# OpenEVSE_PLUS_v1.net
KiCad netlist of a schematic drawn in EAGLE
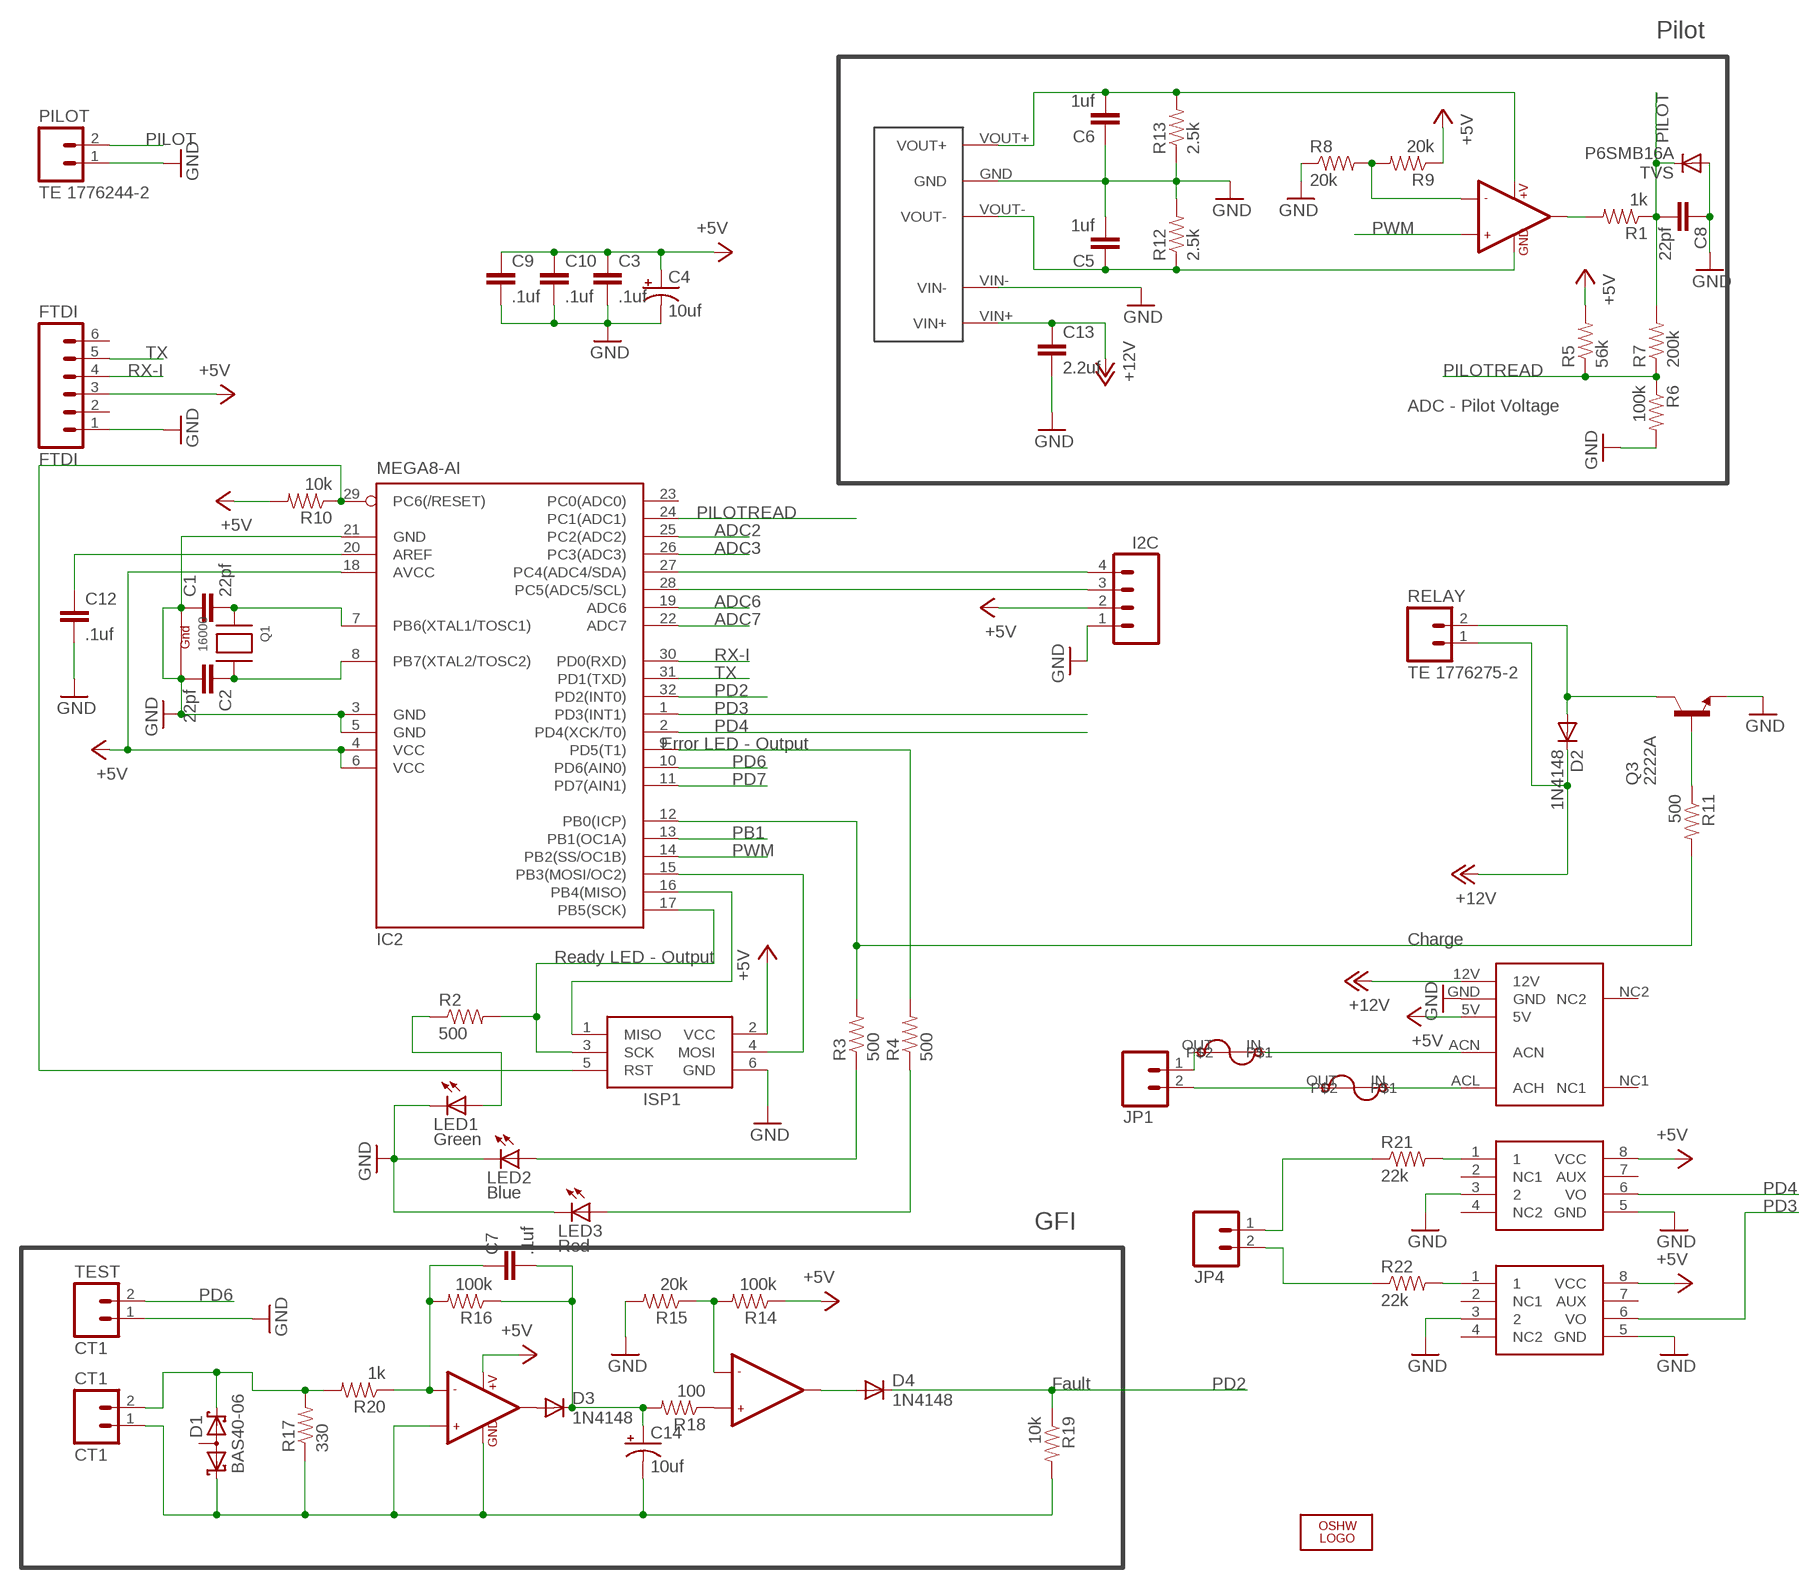
[diagram p0: schematic, sheet 1]

(export (version "E")
  (design (tool "Eeschema 10.0.6"))
  (components
    (comp (ref "C1")
      (value "22pf")
      (footprint "eagle-import:0805")
      (libsource (lib "eagle-import") (part "CAP0805"))
    )
    (comp (ref "C2")
      (value "22pf")
      (footprint "eagle-import:0805")
      (libsource (lib "eagle-import") (part "CAP0805"))
    )
    (comp (ref "C3")
      (value ".1uf")
      (footprint "eagle-import:0805")
      (libsource (lib "eagle-import") (part "CAP0805"))
    )
    (comp (ref "C4")
      (value "10uf")
      (footprint "eagle-import:EIA3216")
      (libsource (lib "eagle-import") (part "CAP_POL1206"))
    )
    (comp (ref "C5")
      (value "1uf")
      (footprint "eagle-import:0805")
      (libsource (lib "eagle-import") (part "CAP0805"))
    )
    (comp (ref "C6")
      (value "1uf")
      (footprint "eagle-import:0805")
      (libsource (lib "eagle-import") (part "CAP0805"))
    )
    (comp (ref "C7")
      (value ".1uf")
      (footprint "eagle-import:0805")
      (libsource (lib "eagle-import") (part "CAP0805"))
    )
    (comp (ref "C8")
      (value "22pf")
      (footprint "eagle-import:0805")
      (libsource (lib "eagle-import") (part "CAP0805"))
    )
    (comp (ref "C9")
      (value ".1uf")
      (footprint "eagle-import:0805")
      (libsource (lib "eagle-import") (part "CAP0805"))
    )
    (comp (ref "C10")
      (value ".1uf")
      (footprint "eagle-import:0805")
      (libsource (lib "eagle-import") (part "CAP0805"))
    )
    (comp (ref "C12")
      (value ".1uf")
      (footprint "eagle-import:0805")
      (libsource (lib "eagle-import") (part "CAP0805"))
    )
    (comp (ref "C13")
      (value "2.2uf")
      (footprint "eagle-import:0805")
      (libsource (lib "eagle-import") (part "CAP0805"))
    )
    (comp (ref "C14")
      (value "10uf")
      (footprint "eagle-import:EIA3216")
      (libsource (lib "eagle-import") (part "CAP_POL1206"))
    )
    (comp (ref "CT1")
      (value "CT1")
      (footprint "eagle-import:1X02_LOCK")
      (libsource (lib "eagle-import") (part "M02LOCK"))
    )
    (comp (ref "D1")
      (value "BAS40-06")
      (footprint "eagle-import:SOT23")
      (libsource (lib "eagle-import") (part "BAS40-06"))
    )
    (comp (ref "D2")
      (value "1N4148")
      (footprint "eagle-import:SOD123")
      (libsource (lib "eagle-import") (part "DIODE-SOD123"))
    )
    (comp (ref "D3")
      (value "1N4148")
      (footprint "eagle-import:SOD123")
      (libsource (lib "eagle-import") (part "DIODE-SOD123"))
    )
    (comp (ref "D4")
      (value "1N4148")
      (footprint "eagle-import:SOD123")
      (libsource (lib "eagle-import") (part "DIODE-SOD123"))
    )
    (comp (ref "DCDC")
      (value "D107E")
      (footprint "eagle-import:DCDC_SIP")
      (libsource (lib "eagle-import") (part "DCDC_SIP"))
    )
    (comp (ref "FTDI")
      (value "FTDI")
      (footprint "eagle-import:1X06_LOCK")
      (libsource (lib "eagle-import") (part "M06LOCK"))
    )
    (comp (ref "I2C")
      (value "M04LOCK")
      (footprint "eagle-import:1X04_LOCK")
      (libsource (lib "eagle-import") (part "M04LOCK"))
    )
    (comp (ref "IC1")
      (value "MID400")
      (footprint "eagle-import:DIP08")
      (libsource (lib "eagle-import") (part "MID400"))
    )
    (comp (ref "IC2")
      (value "MEGA8-AI")
      (footprint "eagle-import:TQFP32-08")
      (fields (field (name "MPN") "ATMEGA8-16AU"))
      (libsource (lib "eagle-import") (part "MEGA8-AI"))
    )
    (comp (ref "IC3")
      (value "LMV358")
      (footprint "eagle-import:SO08")
      (libsource (lib "eagle-import") (part "LMV358"))
    )
    (comp (ref "IC4")
      (value "LMV358")
      (footprint "eagle-import:SO08")
      (libsource (lib "eagle-import") (part "LMV358"))
    )
    (comp (ref "IC5")
      (value "MID400")
      (footprint "eagle-import:DIP08")
      (libsource (lib "eagle-import") (part "MID400"))
    )
    (comp (ref "ISP1")
      (value "AVRISP-6")
      (footprint "eagle-import:AVRISP")
      (libsource (lib "eagle-import") (part "AVRISP-6"))
    )
    (comp (ref "JP1")
      (value "M025MM")
      (footprint "eagle-import:SCREWTERMINAL-5MM-2")
      (libsource (lib "eagle-import") (part "M025MM"))
    )
    (comp (ref "JP4")
      (value "M025MM")
      (footprint "eagle-import:SCREWTERMINAL-5MM-2")
      (libsource (lib "eagle-import") (part "M025MM"))
    )
    (comp (ref "LED1")
      (value "Green")
      (footprint "eagle-import:LED-0603")
      (libsource (lib "eagle-import") (part "LED0603"))
    )
    (comp (ref "LED2")
      (value "Blue")
      (footprint "eagle-import:LED-0603")
      (libsource (lib "eagle-import") (part "LED0603"))
    )
    (comp (ref "LED3")
      (value "Red")
      (footprint "eagle-import:LED-0603")
      (libsource (lib "eagle-import") (part "LED0603"))
    )
    (comp (ref "LOGO1")
      (value "OSHW_LOGO_8MILX0150-NT")
      (footprint "eagle-import:OSHW_8X150_NOTEXT")
      (libsource (lib "eagle-import") (part "OSHW_LOGO_8MILX0150-NT"))
    )
    (comp (ref "PILOT")
      (value "TE 1776244-2")
      (footprint "eagle-import:SCREWTERMINAL-5MM-2")
      (libsource (lib "eagle-import") (part "M025MM"))
    )
    (comp (ref "Q1")
      (value "16000")
      (footprint "eagle-import:NX3225")
      (libsource (lib "eagle-import") (part "XTAL-4-3225"))
    )
    (comp (ref "Q3")
      (value "2222A")
      (footprint "eagle-import:SOT23")
      (libsource (lib "eagle-import") (part "BCX70SMD"))
    )
    (comp (ref "R1")
      (value "1k")
      (footprint "eagle-import:0805")
      (libsource (lib "eagle-import") (part "RESISTOR0805-RES"))
    )
    (comp (ref "R2")
      (value "500")
      (footprint "eagle-import:0805")
      (libsource (lib "eagle-import") (part "RESISTOR0805-RES"))
    )
    (comp (ref "R3")
      (value "500")
      (footprint "eagle-import:0805")
      (libsource (lib "eagle-import") (part "RESISTOR0805-RES"))
    )
    (comp (ref "R4")
      (value "500")
      (footprint "eagle-import:0805")
      (libsource (lib "eagle-import") (part "RESISTOR0805-RES"))
    )
    (comp (ref "R5")
      (value "56k")
      (footprint "eagle-import:0805")
      (libsource (lib "eagle-import") (part "RESISTOR0805-RES"))
    )
    (comp (ref "R6")
      (value "100k")
      (footprint "eagle-import:0805")
      (libsource (lib "eagle-import") (part "RESISTOR0805-RES"))
    )
    (comp (ref "R7")
      (value "200k")
      (footprint "eagle-import:0805")
      (libsource (lib "eagle-import") (part "RESISTOR0805-RES"))
    )
    (comp (ref "R8")
      (value "20k")
      (footprint "eagle-import:0805")
      (libsource (lib "eagle-import") (part "RESISTOR0805-RES"))
    )
    (comp (ref "R9")
      (value "20k")
      (footprint "eagle-import:0805")
      (libsource (lib "eagle-import") (part "RESISTOR0805-RES"))
    )
    (comp (ref "R10")
      (value "10k")
      (footprint "eagle-import:0805")
      (libsource (lib "eagle-import") (part "RESISTOR0805-RES"))
    )
    (comp (ref "R11")
      (value "500")
      (footprint "eagle-import:0805")
      (libsource (lib "eagle-import") (part "RESISTOR0805-RES"))
    )
    (comp (ref "R12")
      (value "2.5k")
      (footprint "eagle-import:0805")
      (libsource (lib "eagle-import") (part "RESISTOR0805-RES"))
    )
    (comp (ref "R13")
      (value "2.5k")
      (footprint "eagle-import:0805")
      (libsource (lib "eagle-import") (part "RESISTOR0805-RES"))
    )
    (comp (ref "R14")
      (value "100k")
      (footprint "eagle-import:0805")
      (libsource (lib "eagle-import") (part "RESISTOR0805-RES"))
    )
    (comp (ref "R15")
      (value "20k")
      (footprint "eagle-import:0805")
      (libsource (lib "eagle-import") (part "RESISTOR0805-RES"))
    )
    (comp (ref "R16")
      (value "100k")
      (footprint "eagle-import:0805")
      (libsource (lib "eagle-import") (part "RESISTOR0805-RES"))
    )
    (comp (ref "R17")
      (value "330")
      (footprint "eagle-import:0805")
      (libsource (lib "eagle-import") (part "RESISTOR0805-RES"))
    )
    (comp (ref "R18")
      (value "100")
      (footprint "eagle-import:0805")
      (libsource (lib "eagle-import") (part "RESISTOR0805-RES"))
    )
    (comp (ref "R19")
      (value "10k")
      (footprint "eagle-import:0805")
      (libsource (lib "eagle-import") (part "RESISTOR0805-RES"))
    )
    (comp (ref "R20")
      (value "1k")
      (footprint "eagle-import:0805")
      (libsource (lib "eagle-import") (part "RESISTOR0805-RES"))
    )
    (comp (ref "R21")
      (value "22k")
      (footprint "eagle-import:AXIAL-0.4")
      (libsource (lib "eagle-import") (part "RESISTORPTH-1/4W"))
    )
    (comp (ref "R22")
      (value "22k")
      (footprint "eagle-import:AXIAL-0.4")
      (libsource (lib "eagle-import") (part "RESISTORPTH-1/4W"))
    )
    (comp (ref "RELAY")
      (value "TE 1776275-2")
      (footprint "eagle-import:SCREWTERMINAL-3.5MM-2_LOCK")
      (libsource (lib "eagle-import") (part "M023.5MM_LOCK"))
    )
    (comp (ref "TEST")
      (value "CT1")
      (footprint "eagle-import:1X02_LOCK")
      (libsource (lib "eagle-import") (part "M02LOCK"))
    )
    (comp (ref "TVS")
      (value "P6SMB16A")
      (footprint "eagle-import:SMB")
      (libsource (lib "eagle-import") (part "DIODE-SMB"))
    )
    (comp (ref "U$1")
      (value "MPM-04E-1205")
      (footprint "eagle-import:MPM-04E-1205")
      (libsource (lib "eagle-import") (part "MPM-04E-1205"))
    )
    (comp (ref "U$2")
      (value "BEL1AFUSE")
      (footprint "eagle-import:BELFUSE1A")
      (libsource (lib "eagle-import") (part "BEL1AFUSE"))
    )
    (comp (ref "U$5")
      (value "BEL1AFUSE")
      (footprint "eagle-import:BELFUSE1A")
      (libsource (lib "eagle-import") (part "BEL1AFUSE"))
    )
  )
  (nets
    (net (code "1") (name "+5V") (class "Default")
      (node (ref "C10") (pin "1") (pinfunction "1_1") (pintype "passive"))
      (node (ref "C3") (pin "1") (pinfunction "1_1") (pintype "passive"))
      (node (ref "C4") (pin "A") (pinfunction "+_A") (pintype "passive"))
      (node (ref "C9") (pin "1") (pinfunction "1_1") (pintype "passive"))
      (node (ref "FTDI") (pin "3") (pinfunction "3_3") (pintype "passive"))
      (node (ref "I2C") (pin "2") (pinfunction "2_2") (pintype "passive"))
      (node (ref "IC1") (pin "8") (pinfunction "VCC_8") (pintype "bidirectional"))
      (node (ref "IC2") (pin "18") (pinfunction "AVCC_18") (pintype "power_in"))
      (node (ref "IC2") (pin "4") (pinfunction "VCC_4") (pintype "power_in"))
      (node (ref "IC2") (pin "6") (pinfunction "VCC_6") (pintype "power_in"))
      (node (ref "IC3") (pin "8") (pinfunction "+V_8") (pintype "power_in"))
      (node (ref "IC5") (pin "8") (pinfunction "VCC_8") (pintype "bidirectional"))
      (node (ref "ISP1") (pin "2") (pinfunction "VCC_2") (pintype "power_in"))
      (node (ref "R10") (pin "2") (pinfunction "2_2") (pintype "passive"))
      (node (ref "R14") (pin "1") (pinfunction "1_1") (pintype "passive"))
      (node (ref "R5") (pin "2") (pinfunction "2_2") (pintype "passive"))
      (node (ref "R9") (pin "1") (pinfunction "1_1") (pintype "passive"))
      (node (ref "U$1") (pin "5V") (pinfunction "5V_5V") (pintype "bidirectional"))
    )
    (net (code "2") (name "+12V") (class "Default")
      (node (ref "C13") (pin "1") (pinfunction "1_1") (pintype "passive"))
      (node (ref "D2") (pin "C") (pinfunction "C_C") (pintype "passive"))
      (node (ref "DCDC") (pin "VIN+") (pinfunction "VIN+_VIN+") (pintype "bidirectional"))
      (node (ref "RELAY") (pin "1") (pinfunction "1_1") (pintype "passive"))
      (node (ref "U$1") (pin "12V") (pinfunction "12V_12V") (pintype "bidirectional"))
    )
    (net (code "3") (name "/ADC2") (class "Default")
      (node (ref "IC2") (pin "25") (pinfunction "PC2(ADC2)_25") (pintype "bidirectional"))
    )
    (net (code "4") (name "/ADC3") (class "Default")
      (node (ref "IC2") (pin "26") (pinfunction "PC3(ADC3)_26") (pintype "bidirectional"))
    )
    (net (code "5") (name "/ADC6") (class "Default")
      (node (ref "IC2") (pin "19") (pinfunction "ADC6_19") (pintype "bidirectional"))
    )
    (net (code "6") (name "/ADC7") (class "Default")
      (node (ref "IC2") (pin "22") (pinfunction "ADC7_22") (pintype "bidirectional"))
    )
    (net (code "7") (name "/PB1") (class "Default")
      (node (ref "IC2") (pin "13") (pinfunction "PB1(OC1A)_13") (pintype "bidirectional"))
    )
    (net (code "8") (name "/PD2") (class "Default")
      (node (ref "D4") (pin "C") (pinfunction "C_C") (pintype "passive"))
      (node (ref "IC2") (pin "32") (pinfunction "PD2(INT0)_32") (pintype "bidirectional"))
      (node (ref "R19") (pin "1") (pinfunction "1_1") (pintype "passive"))
    )
    (net (code "9") (name "/PD3") (class "Default")
      (node (ref "IC2") (pin "1") (pinfunction "PD3(INT1)_1") (pintype "bidirectional"))
      (node (ref "IC5") (pin "6") (pinfunction "VO_6") (pintype "bidirectional"))
    )
    (net (code "10") (name "/PD4") (class "Default")
      (node (ref "IC1") (pin "6") (pinfunction "VO_6") (pintype "bidirectional"))
      (node (ref "IC2") (pin "2") (pinfunction "PD4(XCK/T0)_2") (pintype "bidirectional"))
    )
    (net (code "11") (name "/PD6") (class "Default")
      (node (ref "IC2") (pin "10") (pinfunction "PD6(AIN0)_10") (pintype "bidirectional"))
      (node (ref "TEST") (pin "2") (pinfunction "2_2") (pintype "passive"))
    )
    (net (code "12") (name "/PD7") (class "Default")
      (node (ref "IC2") (pin "11") (pinfunction "PD7(AIN1)_11") (pintype "bidirectional"))
    )
    (net (code "13") (name "/PILOT") (class "Default")
      (node (ref "C8") (pin "2") (pinfunction "2_2") (pintype "passive"))
      (node (ref "PILOT") (pin "2") (pinfunction "2_2") (pintype "passive"))
      (node (ref "R1") (pin "1") (pinfunction "1_1") (pintype "passive"))
      (node (ref "R7") (pin "2") (pinfunction "2_2") (pintype "passive"))
      (node (ref "TVS") (pin "C") (pinfunction "C_C") (pintype "passive"))
    )
    (net (code "14") (name "/PILOTREAD") (class "Default")
      (node (ref "IC2") (pin "24") (pinfunction "PC1(ADC1)_24") (pintype "bidirectional"))
      (node (ref "R5") (pin "1") (pinfunction "1_1") (pintype "passive"))
      (node (ref "R6") (pin "1") (pinfunction "1_1") (pintype "passive"))
      (node (ref "R7") (pin "1") (pinfunction "1_1") (pintype "passive"))
    )
    (net (code "15") (name "/PWM") (class "Default")
      (node (ref "IC2") (pin "14") (pinfunction "PB2(SS/OC1B)_14") (pintype "bidirectional"))
      (node (ref "IC4") (pin "3") (pinfunction "+IN1_3") (pintype "input"))
    )
    (net (code "16") (name "/RX-I") (class "Default")
      (node (ref "FTDI") (pin "4") (pinfunction "4_4") (pintype "passive"))
      (node (ref "IC2") (pin "30") (pinfunction "PD0(RXD)_30") (pintype "bidirectional"))
    )
    (net (code "17") (name "/TX") (class "Default")
      (node (ref "FTDI") (pin "5") (pinfunction "5_5") (pintype "passive"))
      (node (ref "IC2") (pin "31") (pinfunction "PD1(TXD)_31") (pintype "bidirectional"))
    )
    (net (code "18") (name "GND") (class "Default")
      (node (ref "C1") (pin "1") (pinfunction "1_1") (pintype "passive"))
      (node (ref "C10") (pin "2") (pinfunction "2_2") (pintype "passive"))
      (node (ref "C12") (pin "2") (pinfunction "2_2") (pintype "passive"))
      (node (ref "C13") (pin "2") (pinfunction "2_2") (pintype "passive"))
      (node (ref "C2") (pin "2") (pinfunction "2_2") (pintype "passive"))
      (node (ref "C3") (pin "2") (pinfunction "2_2") (pintype "passive"))
      (node (ref "C4") (pin "C") (pinfunction "-_C") (pintype "passive"))
      (node (ref "C5") (pin "2") (pinfunction "2_2") (pintype "passive"))
      (node (ref "C6") (pin "1") (pinfunction "1_1") (pintype "passive"))
      (node (ref "C8") (pin "1") (pinfunction "1_1") (pintype "passive"))
      (node (ref "C9") (pin "2") (pinfunction "2_2") (pintype "passive"))
      (node (ref "DCDC") (pin "GND") (pinfunction "GND_GND") (pintype "bidirectional"))
      (node (ref "DCDC") (pin "VIN-") (pinfunction "VIN-_VIN-") (pintype "bidirectional"))
      (node (ref "FTDI") (pin "1") (pinfunction "1_1") (pintype "passive"))
      (node (ref "I2C") (pin "1") (pinfunction "1_1") (pintype "passive"))
      (node (ref "IC1") (pin "3") (pinfunction "2_3") (pintype "bidirectional"))
      (node (ref "IC1") (pin "5") (pinfunction "GND_5") (pintype "bidirectional"))
      (node (ref "IC2") (pin "21") (pinfunction "GND_21") (pintype "power_in"))
      (node (ref "IC2") (pin "3") (pinfunction "GND_3") (pintype "power_in"))
      (node (ref "IC2") (pin "5") (pinfunction "GND_5") (pintype "power_in"))
      (node (ref "IC5") (pin "3") (pinfunction "2_3") (pintype "bidirectional"))
      (node (ref "IC5") (pin "5") (pinfunction "GND_5") (pintype "bidirectional"))
      (node (ref "ISP1") (pin "6") (pinfunction "GND_6") (pintype "power_in"))
      (node (ref "LED1") (pin "C") (pinfunction "C_C") (pintype "passive"))
      (node (ref "LED2") (pin "C") (pinfunction "C_C") (pintype "passive"))
      (node (ref "LED3") (pin "C") (pinfunction "C_C") (pintype "passive"))
      (node (ref "PILOT") (pin "1") (pinfunction "1_1") (pintype "passive"))
      (node (ref "Q1") (pin "1") (pinfunction "G1_1") (pintype "power_in"))
      (node (ref "Q1") (pin "3") (pinfunction "G2_3") (pintype "power_in"))
      (node (ref "Q3") (pin "2") (pinfunction "E_2") (pintype "passive"))
      (node (ref "R12") (pin "2") (pinfunction "2_2") (pintype "passive"))
      (node (ref "R13") (pin "1") (pinfunction "1_1") (pintype "passive"))
      (node (ref "R15") (pin "2") (pinfunction "2_2") (pintype "passive"))
      (node (ref "R6") (pin "2") (pinfunction "2_2") (pintype "passive"))
      (node (ref "R8") (pin "1") (pinfunction "1_1") (pintype "passive"))
      (node (ref "TEST") (pin "1") (pinfunction "1_1") (pintype "passive"))
      (node (ref "TVS") (pin "A") (pinfunction "A_A") (pintype "passive"))
      (node (ref "U$1") (pin "GND") (pinfunction "GND_GND") (pintype "bidirectional"))
    )
    (net (code "19") (name "Net-(C14-+)") (class "Default")
      (node (ref "C14") (pin "A") (pinfunction "+_A") (pintype "passive"))
      (node (ref "C7") (pin "2") (pinfunction "2_2") (pintype "passive"))
      (node (ref "D3") (pin "C") (pinfunction "C_C") (pintype "passive"))
      (node (ref "R16") (pin "1") (pinfunction "1_1") (pintype "passive"))
      (node (ref "R18") (pin "2") (pinfunction "2_2") (pintype "passive"))
    )
    (net (code "20") (name "Net-(C14--)") (class "Default")
      (node (ref "C14") (pin "C") (pinfunction "-_C") (pintype "passive"))
      (node (ref "CT1") (pin "1") (pinfunction "1_1") (pintype "passive"))
      (node (ref "D1") (pin "1") (pinfunction "K1_1") (pintype "passive"))
      (node (ref "IC3") (pin "3") (pinfunction "+IN1_3") (pintype "input"))
      (node (ref "IC3") (pin "4") (pinfunction "GND_4") (pintype "power_in"))
      (node (ref "R17") (pin "1") (pinfunction "1_1") (pintype "passive"))
      (node (ref "R19") (pin "2") (pinfunction "2_2") (pintype "passive"))
    )
    (net (code "21") (name "Net-(D1-K2)") (class "Default")
      (node (ref "CT1") (pin "2") (pinfunction "2_2") (pintype "passive"))
      (node (ref "D1") (pin "2") (pinfunction "K2_2") (pintype "passive"))
      (node (ref "R17") (pin "2") (pinfunction "2_2") (pintype "passive"))
      (node (ref "R20") (pin "2") (pinfunction "2_2") (pintype "passive"))
    )
    (net (code "22") (name "Net-(IC2-AREF)") (class "Default")
      (node (ref "C12") (pin "1") (pinfunction "1_1") (pintype "passive"))
      (node (ref "IC2") (pin "20") (pinfunction "AREF_20") (pintype "passive"))
    )
    (net (code "23") (name "Net-(IC2-PB0(ICP))") (class "Default")
      (node (ref "IC2") (pin "12") (pinfunction "PB0(ICP)_12") (pintype "bidirectional"))
      (node (ref "R11") (pin "2") (pinfunction "2_2") (pintype "passive"))
      (node (ref "R3") (pin "2") (pinfunction "2_2") (pintype "passive"))
    )
    (net (code "24") (name "Net-(IC2-PB3(MOSI{slash}OC2))") (class "Default")
      (node (ref "IC2") (pin "15") (pinfunction "PB3(MOSI/OC2)_15") (pintype "bidirectional"))
      (node (ref "ISP1") (pin "4") (pinfunction "MOSI_4") (pintype "output"))
    )
    (net (code "25") (name "Net-(IC2-PB4(MISO))") (class "Default")
      (node (ref "IC2") (pin "16") (pinfunction "PB4(MISO)_16") (pintype "bidirectional"))
      (node (ref "ISP1") (pin "1") (pinfunction "MISO_1") (pintype "input"))
    )
    (net (code "26") (name "Net-(IC2-PB5(SCK))") (class "Default")
      (node (ref "IC2") (pin "17") (pinfunction "PB5(SCK)_17") (pintype "bidirectional"))
      (node (ref "ISP1") (pin "3") (pinfunction "SCK_3") (pintype "output"))
      (node (ref "R2") (pin "2") (pinfunction "2_2") (pintype "passive"))
    )
    (net (code "27") (name "Net-(IC2-PB6(XTAL1{slash}TOSC1))") (class "Default")
      (node (ref "C1") (pin "2") (pinfunction "2_2") (pintype "passive"))
      (node (ref "IC2") (pin "7") (pinfunction "PB6(XTAL1/TOSC1)_7") (pintype "bidirectional"))
      (node (ref "Q1") (pin "2") (pinfunction "X1_2") (pintype "bidirectional"))
    )
    (net (code "28") (name "Net-(IC2-PB7(XTAL2{slash}TOSC2))") (class "Default")
      (node (ref "C2") (pin "1") (pinfunction "1_1") (pintype "passive"))
      (node (ref "IC2") (pin "8") (pinfunction "PB7(XTAL2/TOSC2)_8") (pintype "bidirectional"))
      (node (ref "Q1") (pin "4") (pinfunction "X2_4") (pintype "bidirectional"))
    )
    (net (code "29") (name "Net-(IC2-PC4(ADC4{slash}SDA))") (class "Default")
      (node (ref "I2C") (pin "4") (pinfunction "4_4") (pintype "passive"))
      (node (ref "IC2") (pin "27") (pinfunction "PC4(ADC4/SDA)_27") (pintype "bidirectional"))
    )
    (net (code "30") (name "Net-(IC2-PC5(ADC5{slash}SCL))") (class "Default")
      (node (ref "I2C") (pin "3") (pinfunction "3_3") (pintype "passive"))
      (node (ref "IC2") (pin "28") (pinfunction "PC5(ADC5/SCL)_28") (pintype "bidirectional"))
    )
    (net (code "31") (name "Net-(IC2-PC6({slash}RESET))") (class "Default")
      (node (ref "IC2") (pin "29") (pinfunction "PC6(/RESET)_29") (pintype "bidirectional"))
      (node (ref "ISP1") (pin "5") (pinfunction "RST_5") (pintype "output"))
      (node (ref "R10") (pin "1") (pinfunction "1_1") (pintype "passive"))
    )
    (net (code "32") (name "Net-(IC2-PD5(T1))") (class "Default")
      (node (ref "IC2") (pin "9") (pinfunction "PD5(T1)_9") (pintype "bidirectional"))
      (node (ref "R4") (pin "2") (pinfunction "2_2") (pintype "passive"))
    )
    (net (code "33") (name "Net-(IC3A--IN1)") (class "Default")
      (node (ref "C7") (pin "1") (pinfunction "1_1") (pintype "passive"))
      (node (ref "IC3") (pin "2") (pinfunction "-IN1_2") (pintype "input"))
      (node (ref "R16") (pin "2") (pinfunction "2_2") (pintype "passive"))
      (node (ref "R20") (pin "1") (pinfunction "1_1") (pintype "passive"))
    )
    (net (code "34") (name "Net-(IC3A-OUT1)") (class "Default")
      (node (ref "D3") (pin "A") (pinfunction "A_A") (pintype "passive"))
      (node (ref "IC3") (pin "1") (pinfunction "OUT1_1") (pintype "output"))
    )
    (net (code "35") (name "Net-(IC3B-+IN2)") (class "Default")
      (node (ref "IC3") (pin "5") (pinfunction "+IN2_5") (pintype "input"))
      (node (ref "R18") (pin "1") (pinfunction "1_1") (pintype "passive"))
    )
    (net (code "36") (name "Net-(IC3B--IN2)") (class "Default")
      (node (ref "IC3") (pin "6") (pinfunction "-IN2_6") (pintype "input"))
      (node (ref "R14") (pin "2") (pinfunction "2_2") (pintype "passive"))
      (node (ref "R15") (pin "1") (pinfunction "1_1") (pintype "passive"))
    )
    (net (code "37") (name "Net-(IC3B-OUT2)") (class "Default")
      (node (ref "D4") (pin "A") (pinfunction "A_A") (pintype "passive"))
      (node (ref "IC3") (pin "7") (pinfunction "OUT2_7") (pintype "output"))
    )
    (net (code "38") (name "Net-(IC4A-+V)") (class "Default")
      (node (ref "C6") (pin "2") (pinfunction "2_2") (pintype "passive"))
      (node (ref "DCDC") (pin "VOUT+") (pinfunction "VOUT+_VOUT+") (pintype "bidirectional"))
      (node (ref "IC4") (pin "8") (pinfunction "+V_8") (pintype "power_in"))
      (node (ref "R13") (pin "2") (pinfunction "2_2") (pintype "passive"))
    )
    (net (code "39") (name "Net-(IC4A--IN1)") (class "Default")
      (node (ref "IC4") (pin "2") (pinfunction "-IN1_2") (pintype "input"))
      (node (ref "R8") (pin "2") (pinfunction "2_2") (pintype "passive"))
      (node (ref "R9") (pin "2") (pinfunction "2_2") (pintype "passive"))
    )
    (net (code "40") (name "Net-(IC4A-GND)") (class "Default")
      (node (ref "C5") (pin "1") (pinfunction "1_1") (pintype "passive"))
      (node (ref "DCDC") (pin "VOUT-") (pinfunction "VOUT-_VOUT-") (pintype "bidirectional"))
      (node (ref "IC4") (pin "4") (pinfunction "GND_4") (pintype "power_in"))
      (node (ref "R12") (pin "1") (pinfunction "1_1") (pintype "passive"))
    )
    (net (code "41") (name "Net-(IC4A-OUT1)") (class "Default")
      (node (ref "IC4") (pin "1") (pinfunction "OUT1_1") (pintype "output"))
      (node (ref "R1") (pin "2") (pinfunction "2_2") (pintype "passive"))
    )
    (net (code "42") (name "Net-(LED1-PadA)") (class "Default")
      (node (ref "LED1") (pin "A") (pinfunction "A_A") (pintype "passive"))
      (node (ref "R2") (pin "1") (pinfunction "1_1") (pintype "passive"))
    )
    (net (code "43") (name "Net-(LED2-PadA)") (class "Default")
      (node (ref "LED2") (pin "A") (pinfunction "A_A") (pintype "passive"))
      (node (ref "R3") (pin "1") (pinfunction "1_1") (pintype "passive"))
    )
    (net (code "44") (name "Net-(LED3-PadA)") (class "Default")
      (node (ref "LED3") (pin "A") (pinfunction "A_A") (pintype "passive"))
      (node (ref "R4") (pin "1") (pinfunction "1_1") (pintype "passive"))
    )
    (net (code "45") (name "Net-(Q3-B)") (class "Default")
      (node (ref "Q3") (pin "1") (pinfunction "B_1") (pintype "passive"))
      (node (ref "R11") (pin "1") (pinfunction "1_1") (pintype "passive"))
    )
    (net (code "46") (name "Net-(Q3-C)") (class "Default")
      (node (ref "D2") (pin "A") (pinfunction "A_A") (pintype "passive"))
      (node (ref "Q3") (pin "3") (pinfunction "C_3") (pintype "passive"))
      (node (ref "RELAY") (pin "2") (pinfunction "2_2") (pintype "passive"))
    )
    (net (code "47") (name "Net-(R21-1)") (class "Default")
      (node (ref "JP4") (pin "1") (pinfunction "1_1") (pintype "passive"))
      (node (ref "R21") (pin "P$1") (pinfunction "1_P$1") (pintype "passive"))
    )
    (net (code "48") (name "Net-(R21-2)") (class "Default")
      (node (ref "IC1") (pin "1") (pinfunction "1_1") (pintype "bidirectional"))
      (node (ref "R21") (pin "P$2") (pinfunction "2_P$2") (pintype "passive"))
    )
    (net (code "49") (name "Net-(R22-1)") (class "Default")
      (node (ref "JP4") (pin "2") (pinfunction "2_2") (pintype "passive"))
      (node (ref "R22") (pin "P$1") (pinfunction "1_P$1") (pintype "passive"))
    )
    (net (code "50") (name "Net-(R22-2)") (class "Default")
      (node (ref "IC5") (pin "1") (pinfunction "1_1") (pintype "bidirectional"))
      (node (ref "R22") (pin "P$2") (pinfunction "2_P$2") (pintype "passive"))
    )
    (net (code "51") (name "Net-(U$1-ACH)") (class "Default")
      (node (ref "U$1") (pin "ACL") (pinfunction "ACH_ACL") (pintype "bidirectional"))
      (node (ref "U$2") (pin "IN") (pinfunction "P$2_IN") (pintype "bidirectional"))
    )
    (net (code "52") (name "Net-(U$2-P$1)") (class "Default")
      (node (ref "JP1") (pin "2") (pinfunction "2_2") (pintype "passive"))
      (node (ref "U$2") (pin "OUT") (pinfunction "P$1_OUT") (pintype "bidirectional"))
    )
    (net (code "53") (name "Net-(U$5-P$1)") (class "Default")
      (node (ref "JP1") (pin "1") (pinfunction "1_1") (pintype "passive"))
      (node (ref "U$5") (pin "OUT") (pinfunction "P$1_OUT") (pintype "bidirectional"))
    )
    (net (code "54") (name "Net-(U$5-P$2)") (class "Default")
      (node (ref "U$1") (pin "ACN") (pinfunction "ACN_ACN") (pintype "bidirectional"))
      (node (ref "U$5") (pin "IN") (pinfunction "P$2_IN") (pintype "bidirectional"))
    )
    (net (code "55") (name "unconnected-(D1-AA-Pad3)") (class "Default")
      (node (ref "D1") (pin "3") (pinfunction "AA_3") (pintype "passive"))
    )
    (net (code "56") (name "unconnected-(FTDI-Pad2)") (class "Default")
      (node (ref "FTDI") (pin "2") (pinfunction "2_2") (pintype "passive"))
    )
    (net (code "57") (name "unconnected-(FTDI-Pad6)") (class "Default")
      (node (ref "FTDI") (pin "6") (pinfunction "6_6") (pintype "passive"))
    )
    (net (code "58") (name "unconnected-(IC1-AUX-Pad7)") (class "Default")
      (node (ref "IC1") (pin "7") (pinfunction "AUX_7") (pintype "bidirectional"))
    )
    (net (code "59") (name "unconnected-(IC1-NC1-Pad2)") (class "Default")
      (node (ref "IC1") (pin "2") (pinfunction "NC1_2") (pintype "bidirectional"))
    )
    (net (code "60") (name "unconnected-(IC1-NC2-Pad4)") (class "Default")
      (node (ref "IC1") (pin "4") (pinfunction "NC2_4") (pintype "bidirectional"))
    )
    (net (code "61") (name "unconnected-(IC2-PC0(ADC0)-Pad23)") (class "Default")
      (node (ref "IC2") (pin "23") (pinfunction "PC0(ADC0)_23") (pintype "bidirectional"))
    )
    (net (code "62") (name "unconnected-(IC5-AUX-Pad7)") (class "Default")
      (node (ref "IC5") (pin "7") (pinfunction "AUX_7") (pintype "bidirectional"))
    )
    (net (code "63") (name "unconnected-(IC5-NC1-Pad2)") (class "Default")
      (node (ref "IC5") (pin "2") (pinfunction "NC1_2") (pintype "bidirectional"))
    )
    (net (code "64") (name "unconnected-(IC5-NC2-Pad4)") (class "Default")
      (node (ref "IC5") (pin "4") (pinfunction "NC2_4") (pintype "bidirectional"))
    )
    (net (code "65") (name "unconnected-(U$1-PadNC1)") (class "Default")
      (node (ref "U$1") (pin "NC1") (pinfunction "NC1_NC1") (pintype "bidirectional"))
    )
    (net (code "66") (name "unconnected-(U$1-PadNC2)") (class "Default")
      (node (ref "U$1") (pin "NC2") (pinfunction "NC2_NC2") (pintype "bidirectional"))
    )
  )
)
